# RelesOut.net
KiCad netlist of a schematic drawn in Altium Designer
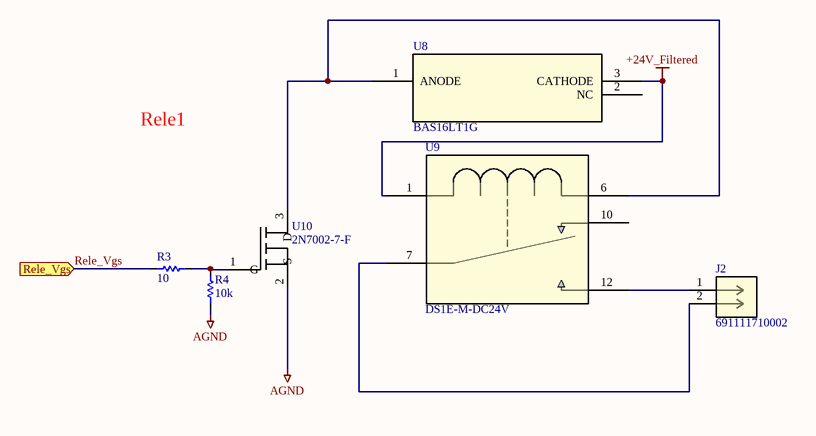
[diagram p0: RelesOut.SchDoc]

(export (version "E")
  (design (tool "Eeschema 10.0.6"))
  (components
    (comp (ref "J2")
      (value "691111710002")
      (footprint "CONN2_710002_WRE")
      (description "No Description Available")
      (fields (field (name "COPYRIGHT") "Copyright (C) 2023 Ultra Librarian. All rights reserved."))
      (libsource (lib "Schlib1") (part "691111710002"))
    )
    (comp (ref "R3")
      (value "10")
      (footprint "RES_0805")
      (description "10 kOhms ±1% 0.125W, 1/8W Chip Resistor 0805 (2012 Metric) Automotive AEC-Q200 Thick Film")
      (fields
        (field (name "MF") "Panasonic Electronic Components")
        (field (name "CREATED") "2020_06_15_DAarancibia")
      )
      (libsource (lib "Schlib1") (part "Res_0805"))
    )
    (comp (ref "R4")
      (value "10k")
      (footprint "RES_0805")
      (description "10 kOhms ±1% 0.125W, 1/8W Chip Resistor 0805 (2012 Metric) Automotive AEC-Q200 Thick Film")
      (fields
        (field (name "MF") "Panasonic Electronic Components")
        (field (name "CREATED") "2020_06_15_DAarancibia")
      )
      (libsource (lib "Schlib1") (part "Res_0805"))
    )
    (comp (ref "U8")
      (value "BAS16LT1G")
      (footprint "SOT-23_ONS-M")
      (description "No Description Available")
      (fields (field (name "COPYRIGHT") "Copyright (C) 2023 Ultra Librarian. All rights reserved."))
      (libsource (lib "Schlib1") (part "BAS16LT1G"))
    )
    (comp (ref "U9")
      (value "DS1E-M-DC24V")
      (footprint "RELAY_DS1E_PAN")
      (description "No Description Available")
      (fields (field (name "COPYRIGHT") "Copyright (C) 2023 Ultra Librarian. All rights reserved."))
      (libsource (lib "Schlib1") (part "DS1E-M-DC24V"))
    )
    (comp (ref "U10")
      (value "2N7002-7-F")
      (footprint "SOT-23_1_DIO")
      (description "No Description Available")
      (libsource (lib "Schlib1") (part "2N7002-7-F"))
    )
  )
  (nets
    (net (code "1") (name "+24V_Filtered") (class "Default")
      (node (ref "U8") (pin "3") (pinfunction "CATHODE_3") (pintype "passive"))
      (node (ref "U9") (pin "1") (pinfunction "1_1") (pintype "passive"))
    )
    (net (code "2") (name "/Rele_Vgs") (class "Default")
      (node (ref "R3") (pin "2") (pinfunction "2_2") (pintype "passive"))
    )
    (net (code "3") (name "AGND") (class "Default")
      (node (ref "R4") (pin "1") (pinfunction "1_1") (pintype "passive"))
      (node (ref "U10") (pin "2") (pinfunction "S_2") (pintype "passive"))
    )
    (net (code "4") (name "Net-(U9-2)") (class "Default")
      (node (ref "J2") (pin "2") (pinfunction "2_2") (pintype "passive"))
      (node (ref "U9") (pin "7") (pinfunction "2_7") (pintype "passive"))
    )
    (net (code "5") (name "Net-(U9-3)") (class "Default")
      (node (ref "J2") (pin "1") (pinfunction "1_1") (pintype "passive"))
      (node (ref "U9") (pin "12") (pinfunction "3_12") (pintype "passive"))
    )
    (net (code "6") (name "Net-(U10-D)") (class "Default")
      (node (ref "U10") (pin "3") (pinfunction "D_3") (pintype "passive"))
      (node (ref "U8") (pin "1") (pinfunction "ANODE_1") (pintype "passive"))
      (node (ref "U9") (pin "6") (pinfunction "5_6") (pintype "passive"))
    )
    (net (code "7") (name "Net-(U10-G)") (class "Default")
      (node (ref "R3") (pin "1") (pinfunction "1_1") (pintype "passive"))
      (node (ref "R4") (pin "2") (pinfunction "2_2") (pintype "passive"))
      (node (ref "U10") (pin "1") (pinfunction "G_1") (pintype "passive"))
    )
    (net (code "8") (name "unconnected-(U8-NC-Pad2)") (class "Default")
      (node (ref "U8") (pin "2") (pinfunction "NC_2") (pintype "passive"))
    )
    (net (code "9") (name "unconnected-(U9-4-Pad10)") (class "Default")
      (node (ref "U9") (pin "10") (pinfunction "4_10") (pintype "passive"))
    )
  )
)
